# Zynq_Programmable_Logic_System.net
KiCad netlist of a schematic drawn in Altium Designer
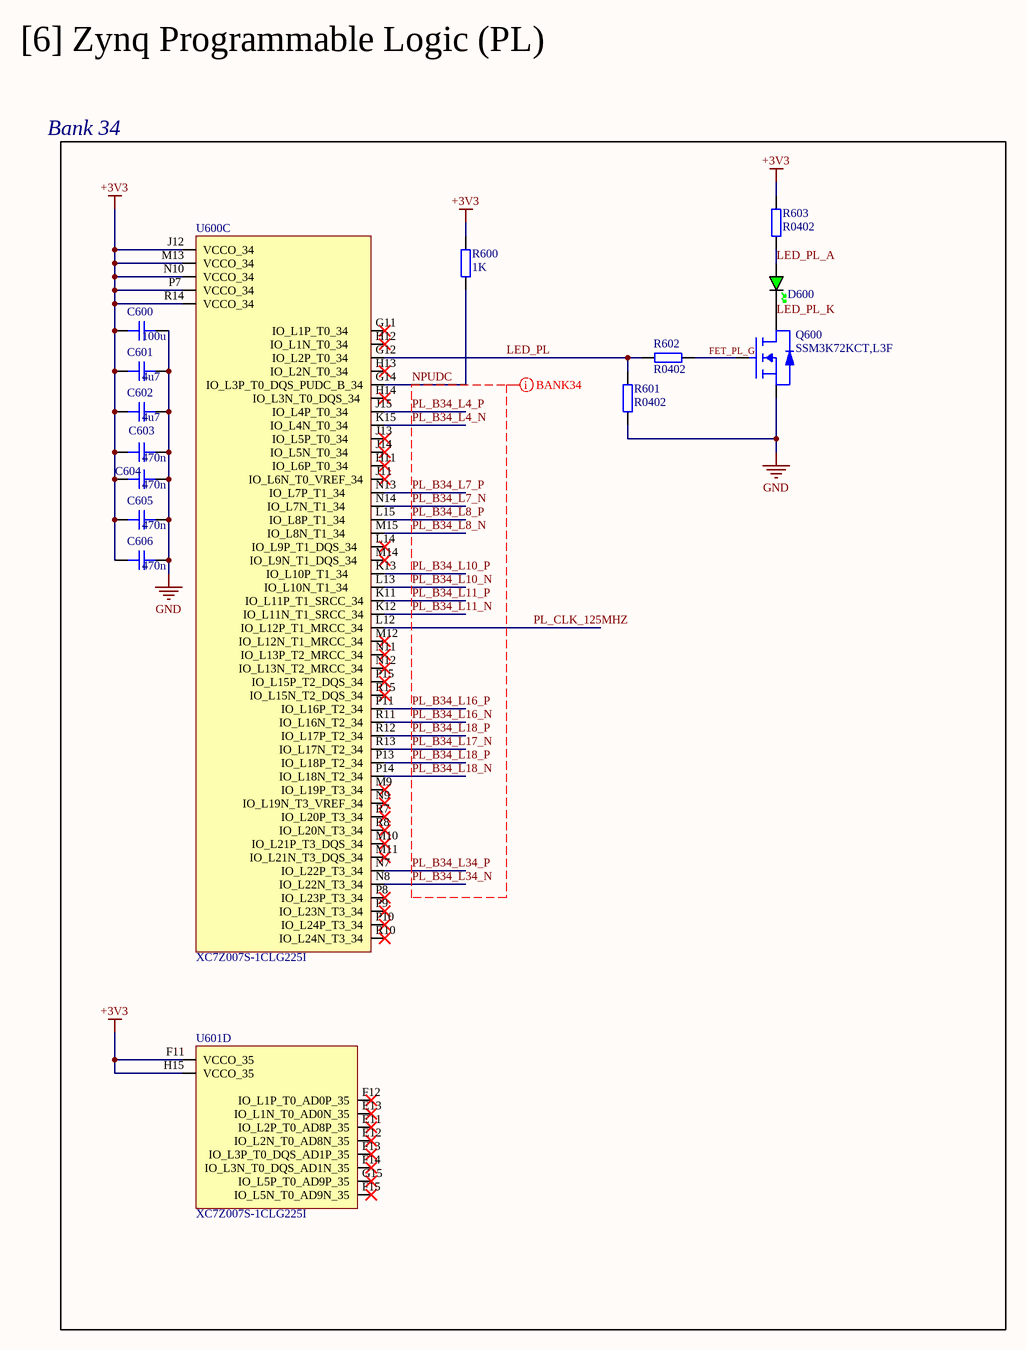
[diagram p0: Zynq Programmable Logic System (PL).SchDoc]

(export (version "E")
  (design (tool "Eeschema 10.0.6"))
  (components
    (comp (ref "C600")
      (value "100u")
      (footprint "CAP_1210")
      (description "Capacitor SMD 1210")
      (libsource (lib "Schematic-Lib-PhilsLab") (part "CAP_1210"))
    )
    (comp (ref "C601")
      (value "4u7")
      (footprint "CAP_1210")
      (description "Capacitor SMD 1210")
      (libsource (lib "Schematic-Lib-PhilsLab") (part "CAP_1210"))
    )
    (comp (ref "C602")
      (value "4u7")
      (footprint "CAP_1210")
      (description "Capacitor SMD 1210")
      (libsource (lib "Schematic-Lib-PhilsLab") (part "CAP_1210"))
    )
    (comp (ref "C603")
      (value "470n")
      (footprint "CAP_1210")
      (description "Capacitor SMD 1210")
      (libsource (lib "Schematic-Lib-PhilsLab") (part "CAP_1210"))
    )
    (comp (ref "C604")
      (value "470n")
      (footprint "CAP_1210")
      (description "Capacitor SMD 1210")
      (libsource (lib "Schematic-Lib-PhilsLab") (part "CAP_1210"))
    )
    (comp (ref "C605")
      (value "470n")
      (footprint "CAP_1210")
      (description "Capacitor SMD 1210")
      (libsource (lib "Schematic-Lib-PhilsLab") (part "CAP_1210"))
    )
    (comp (ref "C606")
      (value "470n")
      (footprint "CAP_1210")
      (description "Capacitor SMD 1210")
      (libsource (lib "Schematic-Lib-PhilsLab") (part "CAP_1210"))
    )
    (comp (ref "D600")
      (value "GREEN")
      (footprint "LED_0402_GREEN")
      (description "LED 0402 GREEN SMD")
      (libsource (lib "Schematic-Lib-PhilsLab") (part "LED_0402_GREEN"))
    )
    (comp (ref "Q600")
      (value "SSM3K72KCT,L3F")
      (footprint "CST3-SOT-883")
      (description "MOSFET N-Channel Vds=60V Id=400mA Rds(on)=1.05R with ESD Protection")
      (fields (field (name "MANUFACTURER") "Toshiba"))
      (libsource (lib "Schematic-Lib-PhilsLab") (part "SSM3K72KCT,L3F"))
    )
    (comp (ref "R600")
      (value "1K")
      (footprint "RES_0402")
      (description "Resistor SMD 0402")
      (libsource (lib "Schematic-Lib-PhilsLab") (part "RES_0402"))
    )
    (comp (ref "R601")
      (value "R0402")
      (footprint "RES_0402")
      (description "Resistor SMD 0402")
      (libsource (lib "Schematic-Lib-PhilsLab") (part "RES_0402"))
    )
    (comp (ref "R602")
      (value "R0402")
      (footprint "RES_0402")
      (description "Resistor SMD 0402")
      (libsource (lib "Schematic-Lib-PhilsLab") (part "RES_0402"))
    )
    (comp (ref "R603")
      (value "R0402")
      (footprint "RES_0402")
      (description "Resistor SMD 0402")
      (libsource (lib "Schematic-Lib-PhilsLab") (part "RES_0402"))
    )
    (comp (ref "U600")
      (value "XC7Z007S-1CLG225I")
      (footprint "CLG225")
      (description "Xilinx FPGA SoC Zynq 7-Series XC7Z007S CLG255 Package Industrial Temperature Grade")
      (fields (field (name "MANUFACTURER") "Xilinx"))
      (libsource (lib "Schematic-Lib-PhilsLab") (part "XC7Z007S-1CLG225I"))
    )
    (comp (ref "U601")
      (value "XC7Z007S-1CLG225I")
      (footprint "CLG225")
      (description "Xilinx FPGA SoC Zynq 7-Series XC7Z007S CLG255 Package Industrial Temperature Grade")
      (fields (field (name "MANUFACTURER") "Xilinx"))
      (libsource (lib "Schematic-Lib-PhilsLab") (part "XC7Z007S-1CLG225I"))
    )
  )
  (nets
    (net (code "1") (name "+3V3") (class "Default")
      (node (ref "C600") (pin "1") (pinfunction "1_1") (pintype "passive"))
      (node (ref "C601") (pin "1") (pinfunction "1_1") (pintype "passive"))
      (node (ref "C602") (pin "1") (pinfunction "1_1") (pintype "passive"))
      (node (ref "C603") (pin "1") (pinfunction "1_1") (pintype "passive"))
      (node (ref "C604") (pin "1") (pinfunction "1_1") (pintype "passive"))
      (node (ref "C605") (pin "1") (pinfunction "1_1") (pintype "passive"))
      (node (ref "C606") (pin "1") (pinfunction "1_1") (pintype "passive"))
      (node (ref "R600") (pin "2") (pinfunction "2_2") (pintype "passive"))
      (node (ref "R603") (pin "2") (pinfunction "2_2") (pintype "passive"))
      (node (ref "U600") (pin "J12") (pinfunction "VCCO_34_J12") (pintype "passive"))
      (node (ref "U600") (pin "M13") (pinfunction "VCCO_34_M13") (pintype "passive"))
      (node (ref "U600") (pin "N10") (pinfunction "VCCO_34_N10") (pintype "passive"))
      (node (ref "U600") (pin "P7") (pinfunction "VCCO_34_P7") (pintype "passive"))
      (node (ref "U600") (pin "R14") (pinfunction "VCCO_34_R14") (pintype "passive"))
      (node (ref "U601") (pin "F11") (pinfunction "VCCO_35_F11") (pintype "passive"))
      (node (ref "U601") (pin "H15") (pinfunction "VCCO_35_H15") (pintype "passive"))
    )
    (net (code "2") (name "/FET_PL_G") (class "Default")
      (node (ref "Q600") (pin "G") (pinfunction "G_G") (pintype "passive"))
      (node (ref "R602") (pin "2") (pinfunction "2_2") (pintype "passive"))
    )
    (net (code "3") (name "/LED_PL") (class "Default")
      (node (ref "R601") (pin "2") (pinfunction "2_2") (pintype "passive"))
      (node (ref "R602") (pin "1") (pinfunction "1_1") (pintype "passive"))
      (node (ref "U600") (pin "G12") (pinfunction "IO_L2P_T0_34_G12") (pintype "passive"))
    )
    (net (code "4") (name "/LED_PL_A") (class "Default")
      (node (ref "D600") (pin "A") (pinfunction "A_A") (pintype "passive"))
      (node (ref "R603") (pin "1") (pinfunction "1_1") (pintype "passive"))
    )
    (net (code "5") (name "/LED_PL_K") (class "Default")
      (node (ref "D600") (pin "K") (pinfunction "K_K") (pintype "passive"))
      (node (ref "Q600") (pin "D") (pinfunction "D_D") (pintype "passive"))
    )
    (net (code "6") (name "/NPUDC") (class "Default")
      (node (ref "R600") (pin "1") (pinfunction "1_1") (pintype "passive"))
      (node (ref "U600") (pin "G14") (pinfunction "IO_L3P_T0_DQS_PUDC_B_34_G14") (pintype "passive"))
    )
    (net (code "7") (name "/PL_B34_L4_N") (class "Default")
      (node (ref "U600") (pin "K15") (pinfunction "IO_L4N_T0_34_K15") (pintype "passive"))
    )
    (net (code "8") (name "/PL_B34_L4_P") (class "Default")
      (node (ref "U600") (pin "J15") (pinfunction "IO_L4P_T0_34_J15") (pintype "passive"))
    )
    (net (code "9") (name "/PL_B34_L7_N") (class "Default")
      (node (ref "U600") (pin "N14") (pinfunction "IO_L7N_T1_34_N14") (pintype "passive"))
    )
    (net (code "10") (name "/PL_B34_L7_P") (class "Default")
      (node (ref "U600") (pin "N13") (pinfunction "IO_L7P_T1_34_N13") (pintype "passive"))
    )
    (net (code "11") (name "/PL_B34_L8_N") (class "Default")
      (node (ref "U600") (pin "M15") (pinfunction "IO_L8N_T1_34_M15") (pintype "passive"))
    )
    (net (code "12") (name "/PL_B34_L8_P") (class "Default")
      (node (ref "U600") (pin "L15") (pinfunction "IO_L8P_T1_34_L15") (pintype "passive"))
    )
    (net (code "13") (name "/PL_B34_L10_N") (class "Default")
      (node (ref "U600") (pin "L13") (pinfunction "IO_L10N_T1_34_L13") (pintype "passive"))
    )
    (net (code "14") (name "/PL_B34_L10_P") (class "Default")
      (node (ref "U600") (pin "K13") (pinfunction "IO_L10P_T1_34_K13") (pintype "passive"))
    )
    (net (code "15") (name "/PL_B34_L11_N") (class "Default")
      (node (ref "U600") (pin "K12") (pinfunction "IO_L11N_T1_SRCC_34_K12") (pintype "passive"))
    )
    (net (code "16") (name "/PL_B34_L11_P") (class "Default")
      (node (ref "U600") (pin "K11") (pinfunction "IO_L11P_T1_SRCC_34_K11") (pintype "passive"))
    )
    (net (code "17") (name "/PL_B34_L16_N") (class "Default")
      (node (ref "U600") (pin "R11") (pinfunction "IO_L16N_T2_34_R11") (pintype "passive"))
    )
    (net (code "18") (name "/PL_B34_L16_P") (class "Default")
      (node (ref "U600") (pin "P11") (pinfunction "IO_L16P_T2_34_P11") (pintype "passive"))
    )
    (net (code "19") (name "/PL_B34_L17_N") (class "Default")
      (node (ref "U600") (pin "R13") (pinfunction "IO_L17N_T2_34_R13") (pintype "passive"))
    )
    (net (code "20") (name "/PL_B34_L18_N") (class "Default")
      (node (ref "U600") (pin "P14") (pinfunction "IO_L18N_T2_34_P14") (pintype "passive"))
    )
    (net (code "21") (name "/PL_B34_L18_P") (class "Default")
      (node (ref "U600") (pin "P13") (pinfunction "IO_L18P_T2_34_P13") (pintype "passive"))
      (node (ref "U600") (pin "R12") (pinfunction "IO_L17P_T2_34_R12") (pintype "passive"))
    )
    (net (code "22") (name "/PL_B34_L34_N") (class "Default")
      (node (ref "U600") (pin "N8") (pinfunction "IO_L22N_T3_34_N8") (pintype "passive"))
    )
    (net (code "23") (name "/PL_B34_L34_P") (class "Default")
      (node (ref "U600") (pin "N7") (pinfunction "IO_L22P_T3_34_N7") (pintype "passive"))
    )
    (net (code "24") (name "/PL_CLK_125MHZ") (class "Default")
      (node (ref "U600") (pin "L12") (pinfunction "IO_L12P_T1_MRCC_34_L12") (pintype "passive"))
    )
    (net (code "25") (name "GND") (class "Default")
      (node (ref "C600") (pin "2") (pinfunction "2_2") (pintype "passive"))
      (node (ref "C601") (pin "2") (pinfunction "2_2") (pintype "passive"))
      (node (ref "C602") (pin "2") (pinfunction "2_2") (pintype "passive"))
      (node (ref "C603") (pin "2") (pinfunction "2_2") (pintype "passive"))
      (node (ref "C604") (pin "2") (pinfunction "2_2") (pintype "passive"))
      (node (ref "C605") (pin "2") (pinfunction "2_2") (pintype "passive"))
      (node (ref "C606") (pin "2") (pinfunction "2_2") (pintype "passive"))
      (node (ref "Q600") (pin "S") (pinfunction "S_S") (pintype "passive"))
      (node (ref "R601") (pin "1") (pinfunction "1_1") (pintype "passive"))
    )
    (net (code "26") (name "unconnected-(U600C-IO_L1N_T0_34-PadH12)") (class "Default")
      (node (ref "U600") (pin "H12") (pinfunction "IO_L1N_T0_34_H12") (pintype "passive+no_connect"))
    )
    (net (code "27") (name "unconnected-(U600C-IO_L1P_T0_34-PadG11)") (class "Default")
      (node (ref "U600") (pin "G11") (pinfunction "IO_L1P_T0_34_G11") (pintype "passive+no_connect"))
    )
    (net (code "28") (name "unconnected-(U600C-IO_L2N_T0_34-PadH13)") (class "Default")
      (node (ref "U600") (pin "H13") (pinfunction "IO_L2N_T0_34_H13") (pintype "passive+no_connect"))
    )
    (net (code "29") (name "unconnected-(U600C-IO_L3N_T0_DQS_34-PadH14)") (class "Default")
      (node (ref "U600") (pin "H14") (pinfunction "IO_L3N_T0_DQS_34_H14") (pintype "passive+no_connect"))
    )
    (net (code "30") (name "unconnected-(U600C-IO_L5N_T0_34-PadJ14)") (class "Default")
      (node (ref "U600") (pin "J14") (pinfunction "IO_L5N_T0_34_J14") (pintype "passive+no_connect"))
    )
    (net (code "31") (name "unconnected-(U600C-IO_L5P_T0_34-PadJ13)") (class "Default")
      (node (ref "U600") (pin "J13") (pinfunction "IO_L5P_T0_34_J13") (pintype "passive+no_connect"))
    )
    (net (code "32") (name "unconnected-(U600C-IO_L6N_T0_VREF_34-PadJ11)") (class "Default")
      (node (ref "U600") (pin "J11") (pinfunction "IO_L6N_T0_VREF_34_J11") (pintype "passive+no_connect"))
    )
    (net (code "33") (name "unconnected-(U600C-IO_L6P_T0_34-PadH11)") (class "Default")
      (node (ref "U600") (pin "H11") (pinfunction "IO_L6P_T0_34_H11") (pintype "passive+no_connect"))
    )
    (net (code "34") (name "unconnected-(U600C-IO_L9N_T1_DQS_34-PadM14)") (class "Default")
      (node (ref "U600") (pin "M14") (pinfunction "IO_L9N_T1_DQS_34_M14") (pintype "passive+no_connect"))
    )
    (net (code "35") (name "unconnected-(U600C-IO_L9P_T1_DQS_34-PadL14)") (class "Default")
      (node (ref "U600") (pin "L14") (pinfunction "IO_L9P_T1_DQS_34_L14") (pintype "passive+no_connect"))
    )
    (net (code "36") (name "unconnected-(U600C-IO_L12N_T1_MRCC_34-PadM12)") (class "Default")
      (node (ref "U600") (pin "M12") (pinfunction "IO_L12N_T1_MRCC_34_M12") (pintype "passive+no_connect"))
    )
    (net (code "37") (name "unconnected-(U600C-IO_L13N_T2_MRCC_34-PadN12)") (class "Default")
      (node (ref "U600") (pin "N12") (pinfunction "IO_L13N_T2_MRCC_34_N12") (pintype "passive+no_connect"))
    )
    (net (code "38") (name "unconnected-(U600C-IO_L13P_T2_MRCC_34-PadN11)") (class "Default")
      (node (ref "U600") (pin "N11") (pinfunction "IO_L13P_T2_MRCC_34_N11") (pintype "passive+no_connect"))
    )
    (net (code "39") (name "unconnected-(U600C-IO_L15N_T2_DQS_34-PadR15)") (class "Default")
      (node (ref "U600") (pin "R15") (pinfunction "IO_L15N_T2_DQS_34_R15") (pintype "passive+no_connect"))
    )
    (net (code "40") (name "unconnected-(U600C-IO_L15P_T2_DQS_34-PadP15)") (class "Default")
      (node (ref "U600") (pin "P15") (pinfunction "IO_L15P_T2_DQS_34_P15") (pintype "passive+no_connect"))
    )
    (net (code "41") (name "unconnected-(U600C-IO_L19N_T3_VREF_34-PadN9)") (class "Default")
      (node (ref "U600") (pin "N9") (pinfunction "IO_L19N_T3_VREF_34_N9") (pintype "passive+no_connect"))
    )
    (net (code "42") (name "unconnected-(U600C-IO_L19P_T3_34-PadM9)") (class "Default")
      (node (ref "U600") (pin "M9") (pinfunction "IO_L19P_T3_34_M9") (pintype "passive+no_connect"))
    )
    (net (code "43") (name "unconnected-(U600C-IO_L20N_T3_34-PadR8)") (class "Default")
      (node (ref "U600") (pin "R8") (pinfunction "IO_L20N_T3_34_R8") (pintype "passive+no_connect"))
    )
    (net (code "44") (name "unconnected-(U600C-IO_L20P_T3_34-PadR7)") (class "Default")
      (node (ref "U600") (pin "R7") (pinfunction "IO_L20P_T3_34_R7") (pintype "passive+no_connect"))
    )
    (net (code "45") (name "unconnected-(U600C-IO_L21N_T3_DQS_34-PadM11)") (class "Default")
      (node (ref "U600") (pin "M11") (pinfunction "IO_L21N_T3_DQS_34_M11") (pintype "passive+no_connect"))
    )
    (net (code "46") (name "unconnected-(U600C-IO_L21P_T3_DQS_34-PadM10)") (class "Default")
      (node (ref "U600") (pin "M10") (pinfunction "IO_L21P_T3_DQS_34_M10") (pintype "passive+no_connect"))
    )
    (net (code "47") (name "unconnected-(U600C-IO_L23N_T3_34-PadP9)") (class "Default")
      (node (ref "U600") (pin "P9") (pinfunction "IO_L23N_T3_34_P9") (pintype "passive+no_connect"))
    )
    (net (code "48") (name "unconnected-(U600C-IO_L23P_T3_34-PadP8)") (class "Default")
      (node (ref "U600") (pin "P8") (pinfunction "IO_L23P_T3_34_P8") (pintype "passive+no_connect"))
    )
    (net (code "49") (name "unconnected-(U600C-IO_L24N_T3_34-PadR10)") (class "Default")
      (node (ref "U600") (pin "R10") (pinfunction "IO_L24N_T3_34_R10") (pintype "passive+no_connect"))
    )
    (net (code "50") (name "unconnected-(U600C-IO_L24P_T3_34-PadP10)") (class "Default")
      (node (ref "U600") (pin "P10") (pinfunction "IO_L24P_T3_34_P10") (pintype "passive+no_connect"))
    )
    (net (code "51") (name "unconnected-(U601D-IO_L1N_T0_AD0N_35-PadE13)") (class "Default")
      (node (ref "U601") (pin "E13") (pinfunction "IO_L1N_T0_AD0N_35_E13") (pintype "passive+no_connect"))
    )
    (net (code "52") (name "unconnected-(U601D-IO_L1P_T0_AD0P_35-PadF12)") (class "Default")
      (node (ref "U601") (pin "F12") (pinfunction "IO_L1P_T0_AD0P_35_F12") (pintype "passive+no_connect"))
    )
    (net (code "53") (name "unconnected-(U601D-IO_L2N_T0_AD8N_35-PadE12)") (class "Default")
      (node (ref "U601") (pin "E12") (pinfunction "IO_L2N_T0_AD8N_35_E12") (pintype "passive+no_connect"))
    )
    (net (code "54") (name "unconnected-(U601D-IO_L2P_T0_AD8P_35-PadE11)") (class "Default")
      (node (ref "U601") (pin "E11") (pinfunction "IO_L2P_T0_AD8P_35_E11") (pintype "passive+no_connect"))
    )
    (net (code "55") (name "unconnected-(U601D-IO_L3N_T0_DQS_AD1N_35-PadF14)") (class "Default")
      (node (ref "U601") (pin "F14") (pinfunction "IO_L3N_T0_DQS_AD1N_35_F14") (pintype "passive+no_connect"))
    )
    (net (code "56") (name "unconnected-(U601D-IO_L3P_T0_DQS_AD1P_35-PadF13)") (class "Default")
      (node (ref "U601") (pin "F13") (pinfunction "IO_L3P_T0_DQS_AD1P_35_F13") (pintype "passive+no_connect"))
    )
    (net (code "57") (name "unconnected-(U601D-IO_L5N_T0_AD9N_35-PadF15)") (class "Default")
      (node (ref "U601") (pin "F15") (pinfunction "IO_L5N_T0_AD9N_35_F15") (pintype "passive+no_connect"))
    )
    (net (code "58") (name "unconnected-(U601D-IO_L5P_T0_AD9P_35-PadG15)") (class "Default")
      (node (ref "U601") (pin "G15") (pinfunction "IO_L5P_T0_AD9P_35_G15") (pintype "passive+no_connect"))
    )
  )
)
